# 02_BTB_IO.net
KiCad netlist of a schematic drawn in Altium Designer
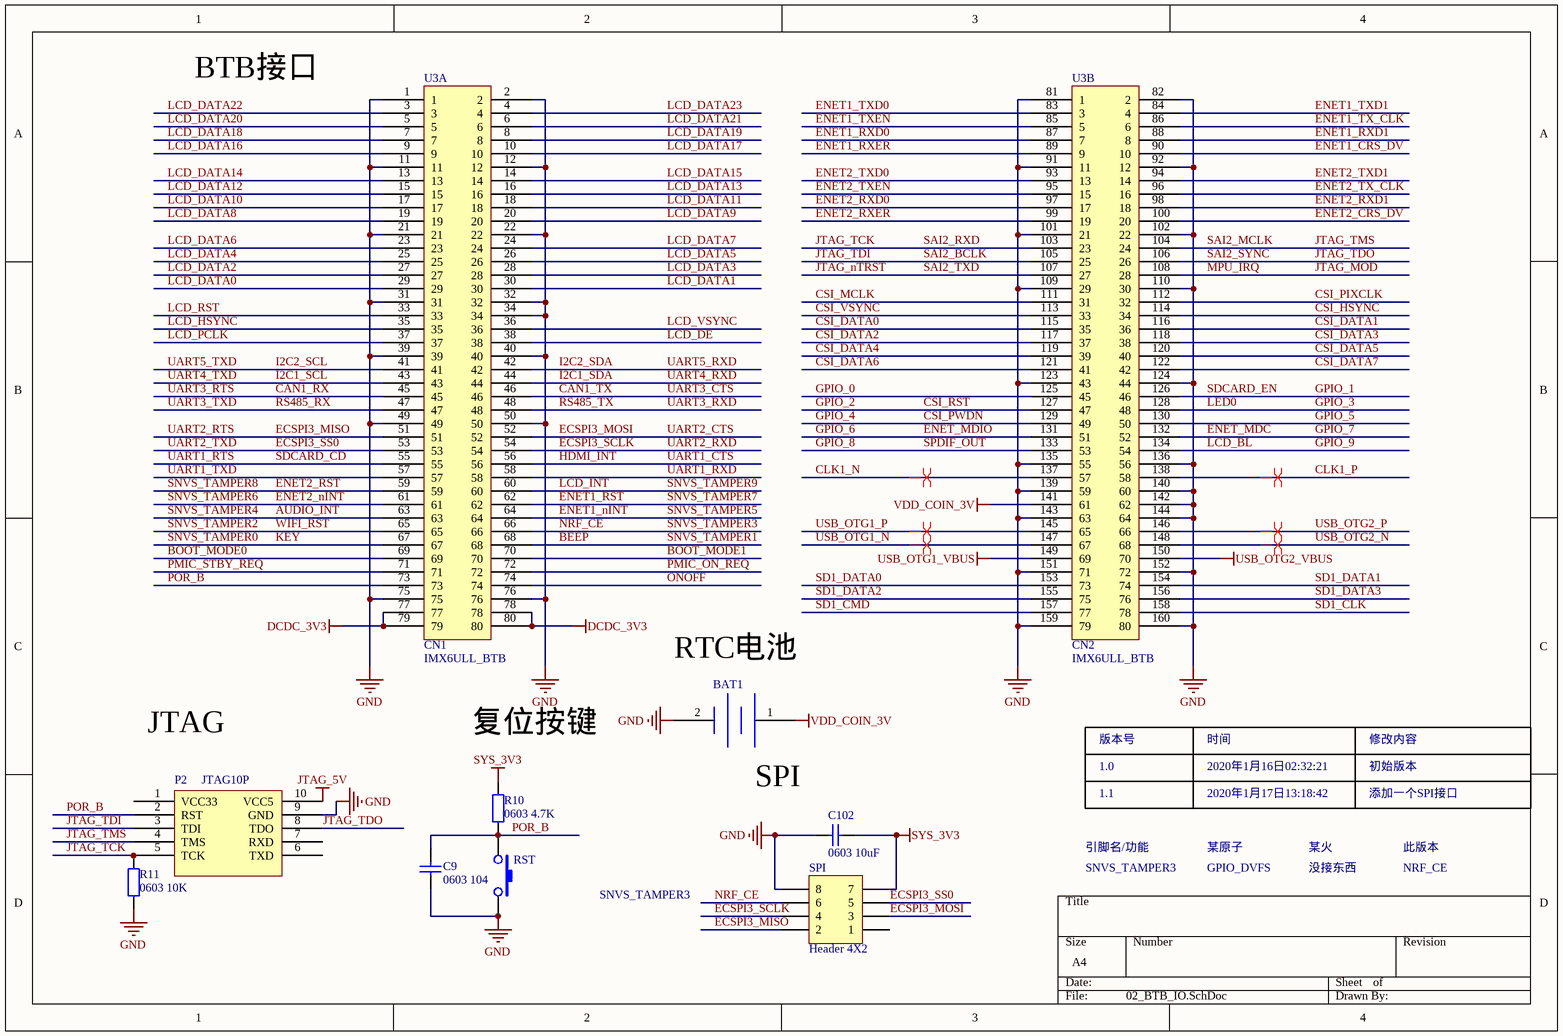
[diagram p0: 02_BTB_IO.SchDoc]

(export (version "E")
  (design (tool "Eeschema 10.0.6"))
  (components
    (comp (ref "BAT1")
      (value "~")
      (footprint "CR1220")
      (libsource (lib "Integrated_Library2") (part "RTC电池"))
    )
    (comp (ref "C9")
      (value "0603 104")
      (footprint "LC-0603_C")
      (description "贴片电容")
      (libsource (lib "JLC") (part "0603 1.5nF (152) 10% 50V"))
    )
    (comp (ref "C102")
      (value "0603 10uF")
      (footprint "LC-0603_C")
      (description "贴片电容")
      (libsource (lib "JLC") (part "0603 1.5nF (152) 10% 50V"))
    )
    (comp (ref "P2")
      (value "JTAG10P")
      (footprint "JTAG10P2")
      (libsource (lib "Integrated_Library2") (part "JTAG10P"))
    )
    (comp (ref "R10")
      (value "0603 4.7K")
      (footprint "LC-0603_R")
      (description "贴片电阻")
      (libsource (lib "JLC") (part "0603 1.1KΩ (1101) 1%"))
    )
    (comp (ref "R11")
      (value "0603 10K")
      (footprint "LC-0603_R")
      (description "贴片电阻")
      (libsource (lib "JLC") (part "0603 1.1KΩ (1101) 1%"))
    )
    (comp (ref "RST") (value "~") (footprint "KEY2") (libsource (lib "Integrated_Library2") (part "KEY")))
    (comp (ref "SPI")
      (value "Header 4X2")
      (footprint "HDR2X4")
      (description "Header, 4-Pin, Dual row")
      (fields (field (name "PUBLISHER") "Altium Limited"))
      (libsource (lib "Miscellaneous Connectors") (part "Header 4X2"))
    )
    (comp (ref "U3")
      (value "IMX6ULL_BTB")
      (footprint "IMX6ULL_BTB")
      (libsource (lib "Integrated_Library2") (part "IMX6ULL_BTB"))
    )
  )
  (nets
    (net (code "1") (name "/AUDIO_INT") (class "Default")
      (node (ref "U3") (pin "63") (pinfunction "63_63") (pintype "passive"))
    )
    (net (code "2") (name "/BEEP") (class "Default")
      (node (ref "U3") (pin "68") (pinfunction "68_68") (pintype "passive"))
    )
    (net (code "3") (name "/BOOT_MODE0") (class "Default")
      (node (ref "U3") (pin "69") (pinfunction "69_69") (pintype "passive"))
    )
    (net (code "4") (name "/BOOT_MODE1") (class "Default")
      (node (ref "U3") (pin "70") (pinfunction "70_70") (pintype "passive"))
    )
    (net (code "5") (name "/CAN1_RX") (class "Default")
      (node (ref "U3") (pin "45") (pinfunction "45_45") (pintype "passive"))
    )
    (net (code "6") (name "/CAN1_TX") (class "Default")
      (node (ref "U3") (pin "46") (pinfunction "46_46") (pintype "passive"))
    )
    (net (code "7") (name "/CLK1_N") (class "Default")
      (node (ref "U3") (pin "137") (pinfunction "57_137") (pintype "passive"))
    )
    (net (code "8") (name "/CLK1_P") (class "Default")
      (node (ref "U3") (pin "138") (pinfunction "58_138") (pintype "passive"))
    )
    (net (code "9") (name "/CSI_DATA0") (class "Default")
      (node (ref "U3") (pin "115") (pinfunction "35_115") (pintype "passive"))
    )
    (net (code "10") (name "/CSI_DATA1") (class "Default")
      (node (ref "U3") (pin "116") (pinfunction "36_116") (pintype "passive"))
    )
    (net (code "11") (name "/CSI_DATA2") (class "Default")
      (node (ref "U3") (pin "117") (pinfunction "37_117") (pintype "passive"))
    )
    (net (code "12") (name "/CSI_DATA3") (class "Default")
      (node (ref "U3") (pin "118") (pinfunction "38_118") (pintype "passive"))
    )
    (net (code "13") (name "/CSI_DATA4") (class "Default")
      (node (ref "U3") (pin "119") (pinfunction "39_119") (pintype "passive"))
    )
    (net (code "14") (name "/CSI_DATA5") (class "Default")
      (node (ref "U3") (pin "120") (pinfunction "40_120") (pintype "passive"))
    )
    (net (code "15") (name "/CSI_DATA6") (class "Default")
      (node (ref "U3") (pin "121") (pinfunction "41_121") (pintype "passive"))
    )
    (net (code "16") (name "/CSI_DATA7") (class "Default")
      (node (ref "U3") (pin "122") (pinfunction "42_122") (pintype "passive"))
    )
    (net (code "17") (name "/CSI_HSYNC") (class "Default")
      (node (ref "U3") (pin "114") (pinfunction "34_114") (pintype "passive"))
    )
    (net (code "18") (name "/CSI_MCLK") (class "Default")
      (node (ref "U3") (pin "111") (pinfunction "31_111") (pintype "passive"))
    )
    (net (code "19") (name "/CSI_PIXCLK") (class "Default")
      (node (ref "U3") (pin "112") (pinfunction "32_112") (pintype "passive"))
    )
    (net (code "20") (name "/CSI_PWDN") (class "Default")
      (node (ref "U3") (pin "129") (pinfunction "49_129") (pintype "passive"))
    )
    (net (code "21") (name "/CSI_RST") (class "Default")
      (node (ref "U3") (pin "127") (pinfunction "47_127") (pintype "passive"))
    )
    (net (code "22") (name "/CSI_VSYNC") (class "Default")
      (node (ref "U3") (pin "113") (pinfunction "33_113") (pintype "passive"))
    )
    (net (code "23") (name "/ECSPI3_MISO") (class "Default")
      (node (ref "SPI") (pin "2") (pinfunction "2_2") (pintype "passive"))
      (node (ref "U3") (pin "51") (pinfunction "51_51") (pintype "passive"))
    )
    (net (code "24") (name "/ECSPI3_MOSI") (class "Default")
      (node (ref "SPI") (pin "3") (pinfunction "3_3") (pintype "passive"))
      (node (ref "U3") (pin "52") (pinfunction "52_52") (pintype "passive"))
    )
    (net (code "25") (name "/ECSPI3_SCLK") (class "Default")
      (node (ref "SPI") (pin "4") (pinfunction "4_4") (pintype "passive"))
      (node (ref "U3") (pin "54") (pinfunction "54_54") (pintype "passive"))
    )
    (net (code "26") (name "/ECSPI3_SS0") (class "Default")
      (node (ref "SPI") (pin "5") (pinfunction "5_5") (pintype "passive"))
      (node (ref "U3") (pin "53") (pinfunction "53_53") (pintype "passive"))
    )
    (net (code "27") (name "/ENET1_CRS_DV") (class "Default")
      (node (ref "U3") (pin "90") (pinfunction "10_90") (pintype "passive"))
    )
    (net (code "28") (name "/ENET1_RST") (class "Default")
      (node (ref "U3") (pin "62") (pinfunction "62_62") (pintype "passive"))
    )
    (net (code "29") (name "/ENET1_RXD0") (class "Default")
      (node (ref "U3") (pin "87") (pinfunction "7_87") (pintype "passive"))
    )
    (net (code "30") (name "/ENET1_RXD1") (class "Default")
      (node (ref "U3") (pin "88") (pinfunction "8_88") (pintype "passive"))
    )
    (net (code "31") (name "/ENET1_RXER") (class "Default")
      (node (ref "U3") (pin "89") (pinfunction "9_89") (pintype "passive"))
    )
    (net (code "32") (name "/ENET1_TXD0") (class "Default")
      (node (ref "U3") (pin "83") (pinfunction "3_83") (pintype "passive"))
    )
    (net (code "33") (name "/ENET1_TXD1") (class "Default")
      (node (ref "U3") (pin "84") (pinfunction "4_84") (pintype "passive"))
    )
    (net (code "34") (name "/ENET1_TXEN") (class "Default")
      (node (ref "U3") (pin "85") (pinfunction "5_85") (pintype "passive"))
    )
    (net (code "35") (name "/ENET1_TX_CLK") (class "Default")
      (node (ref "U3") (pin "86") (pinfunction "6_86") (pintype "passive"))
    )
    (net (code "36") (name "/ENET1_nINT") (class "Default")
      (node (ref "U3") (pin "64") (pinfunction "64_64") (pintype "passive"))
    )
    (net (code "37") (name "/ENET2_CRS_DV") (class "Default")
      (node (ref "U3") (pin "100") (pinfunction "20_100") (pintype "passive"))
    )
    (net (code "38") (name "/ENET2_RST") (class "Default")
      (node (ref "U3") (pin "59") (pinfunction "59_59") (pintype "passive"))
    )
    (net (code "39") (name "/ENET2_RXD0") (class "Default")
      (node (ref "U3") (pin "97") (pinfunction "17_97") (pintype "passive"))
    )
    (net (code "40") (name "/ENET2_RXD1") (class "Default")
      (node (ref "U3") (pin "98") (pinfunction "18_98") (pintype "passive"))
    )
    (net (code "41") (name "/ENET2_RXER") (class "Default")
      (node (ref "U3") (pin "99") (pinfunction "19_99") (pintype "passive"))
    )
    (net (code "42") (name "/ENET2_TXD0") (class "Default")
      (node (ref "U3") (pin "93") (pinfunction "13_93") (pintype "passive"))
    )
    (net (code "43") (name "/ENET2_TXD1") (class "Default")
      (node (ref "U3") (pin "94") (pinfunction "14_94") (pintype "passive"))
    )
    (net (code "44") (name "/ENET2_TXEN") (class "Default")
      (node (ref "U3") (pin "95") (pinfunction "15_95") (pintype "passive"))
    )
    (net (code "45") (name "/ENET2_TX_CLK") (class "Default")
      (node (ref "U3") (pin "96") (pinfunction "16_96") (pintype "passive"))
    )
    (net (code "46") (name "/ENET2_nINT") (class "Default")
      (node (ref "U3") (pin "61") (pinfunction "61_61") (pintype "passive"))
    )
    (net (code "47") (name "/ENET_MDC") (class "Default")
      (node (ref "U3") (pin "132") (pinfunction "52_132") (pintype "passive"))
    )
    (net (code "48") (name "/ENET_MDIO") (class "Default")
      (node (ref "U3") (pin "131") (pinfunction "51_131") (pintype "passive"))
    )
    (net (code "49") (name "/GPIO_0") (class "Default")
      (node (ref "U3") (pin "125") (pinfunction "45_125") (pintype "passive"))
    )
    (net (code "50") (name "/GPIO_1") (class "Default")
      (node (ref "U3") (pin "126") (pinfunction "46_126") (pintype "passive"))
    )
    (net (code "51") (name "/GPIO_3") (class "Default")
      (node (ref "U3") (pin "128") (pinfunction "48_128") (pintype "passive"))
    )
    (net (code "52") (name "/GPIO_5") (class "Default")
      (node (ref "U3") (pin "130") (pinfunction "50_130") (pintype "passive"))
    )
    (net (code "53") (name "/GPIO_8") (class "Default")
      (node (ref "U3") (pin "133") (pinfunction "53_133") (pintype "passive"))
    )
    (net (code "54") (name "/GPIO_9") (class "Default")
      (node (ref "U3") (pin "134") (pinfunction "54_134") (pintype "passive"))
    )
    (net (code "55") (name "/HDMI_INT") (class "Default")
      (node (ref "U3") (pin "56") (pinfunction "56_56") (pintype "passive"))
    )
    (net (code "56") (name "/I2C1_SCL") (class "Default")
      (node (ref "U3") (pin "43") (pinfunction "43_43") (pintype "passive"))
    )
    (net (code "57") (name "/I2C1_SDA") (class "Default")
      (node (ref "U3") (pin "44") (pinfunction "44_44") (pintype "passive"))
    )
    (net (code "58") (name "/I2C2_SCL") (class "Default")
      (node (ref "U3") (pin "41") (pinfunction "41_41") (pintype "passive"))
    )
    (net (code "59") (name "/I2C2_SDA") (class "Default")
      (node (ref "U3") (pin "42") (pinfunction "42_42") (pintype "passive"))
    )
    (net (code "60") (name "/JTAG_MOD") (class "Default")
      (node (ref "U3") (pin "108") (pinfunction "28_108") (pintype "passive"))
    )
    (net (code "61") (name "/JTAG_TCK") (class "Default")
      (node (ref "P2") (pin "5") (pinfunction "TCK_5") (pintype "passive"))
      (node (ref "R11") (pin "2") (pinfunction "2_2") (pintype "passive"))
      (node (ref "U3") (pin "103") (pinfunction "23_103") (pintype "passive"))
    )
    (net (code "62") (name "/JTAG_TDI") (class "Default")
      (node (ref "P2") (pin "3") (pinfunction "TDI_3") (pintype "passive"))
      (node (ref "U3") (pin "105") (pinfunction "25_105") (pintype "passive"))
    )
    (net (code "63") (name "/JTAG_TDO") (class "Default")
      (node (ref "P2") (pin "8") (pinfunction "TDO_8") (pintype "passive"))
      (node (ref "U3") (pin "106") (pinfunction "26_106") (pintype "passive"))
    )
    (net (code "64") (name "/JTAG_TMS") (class "Default")
      (node (ref "P2") (pin "4") (pinfunction "TMS_4") (pintype "passive"))
      (node (ref "U3") (pin "104") (pinfunction "24_104") (pintype "passive"))
    )
    (net (code "65") (name "/JTAG_nTRST") (class "Default")
      (node (ref "U3") (pin "107") (pinfunction "27_107") (pintype "passive"))
    )
    (net (code "66") (name "/KEY") (class "Default")
      (node (ref "U3") (pin "67") (pinfunction "67_67") (pintype "passive"))
    )
    (net (code "67") (name "/LCD_DATA0") (class "Default")
      (node (ref "U3") (pin "29") (pinfunction "29_29") (pintype "passive"))
    )
    (net (code "68") (name "/LCD_DATA1") (class "Default")
      (node (ref "U3") (pin "30") (pinfunction "30_30") (pintype "passive"))
    )
    (net (code "69") (name "/LCD_DATA2") (class "Default")
      (node (ref "U3") (pin "27") (pinfunction "27_27") (pintype "passive"))
    )
    (net (code "70") (name "/LCD_DATA3") (class "Default")
      (node (ref "U3") (pin "28") (pinfunction "28_28") (pintype "passive"))
    )
    (net (code "71") (name "/LCD_DATA4") (class "Default")
      (node (ref "U3") (pin "25") (pinfunction "25_25") (pintype "passive"))
    )
    (net (code "72") (name "/LCD_DATA5") (class "Default")
      (node (ref "U3") (pin "26") (pinfunction "26_26") (pintype "passive"))
    )
    (net (code "73") (name "/LCD_DATA6") (class "Default")
      (node (ref "U3") (pin "23") (pinfunction "23_23") (pintype "passive"))
    )
    (net (code "74") (name "/LCD_DATA7") (class "Default")
      (node (ref "U3") (pin "24") (pinfunction "24_24") (pintype "passive"))
    )
    (net (code "75") (name "/LCD_DATA8") (class "Default")
      (node (ref "U3") (pin "19") (pinfunction "19_19") (pintype "passive"))
    )
    (net (code "76") (name "/LCD_DATA9") (class "Default")
      (node (ref "U3") (pin "20") (pinfunction "20_20") (pintype "passive"))
    )
    (net (code "77") (name "/LCD_DATA10") (class "Default")
      (node (ref "U3") (pin "17") (pinfunction "17_17") (pintype "passive"))
    )
    (net (code "78") (name "/LCD_DATA11") (class "Default")
      (node (ref "U3") (pin "18") (pinfunction "18_18") (pintype "passive"))
    )
    (net (code "79") (name "/LCD_DATA12") (class "Default")
      (node (ref "U3") (pin "15") (pinfunction "15_15") (pintype "passive"))
    )
    (net (code "80") (name "/LCD_DATA13") (class "Default")
      (node (ref "U3") (pin "16") (pinfunction "16_16") (pintype "passive"))
    )
    (net (code "81") (name "/LCD_DATA14") (class "Default")
      (node (ref "U3") (pin "13") (pinfunction "13_13") (pintype "passive"))
    )
    (net (code "82") (name "/LCD_DATA15") (class "Default")
      (node (ref "U3") (pin "14") (pinfunction "14_14") (pintype "passive"))
    )
    (net (code "83") (name "/LCD_DATA16") (class "Default")
      (node (ref "U3") (pin "9") (pinfunction "9_9") (pintype "passive"))
    )
    (net (code "84") (name "/LCD_DATA17") (class "Default")
      (node (ref "U3") (pin "10") (pinfunction "10_10") (pintype "passive"))
    )
    (net (code "85") (name "/LCD_DATA18") (class "Default")
      (node (ref "U3") (pin "7") (pinfunction "7_7") (pintype "passive"))
    )
    (net (code "86") (name "/LCD_DATA19") (class "Default")
      (node (ref "U3") (pin "8") (pinfunction "8_8") (pintype "passive"))
    )
    (net (code "87") (name "/LCD_DATA20") (class "Default")
      (node (ref "U3") (pin "5") (pinfunction "5_5") (pintype "passive"))
    )
    (net (code "88") (name "/LCD_DATA21") (class "Default")
      (node (ref "U3") (pin "6") (pinfunction "6_6") (pintype "passive"))
    )
    (net (code "89") (name "/LCD_DATA22") (class "Default")
      (node (ref "U3") (pin "3") (pinfunction "3_3") (pintype "passive"))
    )
    (net (code "90") (name "/LCD_DATA23") (class "Default")
      (node (ref "U3") (pin "4") (pinfunction "4_4") (pintype "passive"))
    )
    (net (code "91") (name "/LCD_DE") (class "Default")
      (node (ref "U3") (pin "38") (pinfunction "38_38") (pintype "passive"))
    )
    (net (code "92") (name "/LCD_HSYNC") (class "Default")
      (node (ref "U3") (pin "35") (pinfunction "35_35") (pintype "passive"))
    )
    (net (code "93") (name "/LCD_INT") (class "Default")
      (node (ref "U3") (pin "60") (pinfunction "60_60") (pintype "passive"))
    )
    (net (code "94") (name "/LCD_PCLK") (class "Default")
      (node (ref "U3") (pin "37") (pinfunction "37_37") (pintype "passive"))
    )
    (net (code "95") (name "/LCD_RST") (class "Default")
      (node (ref "U3") (pin "33") (pinfunction "33_33") (pintype "passive"))
    )
    (net (code "96") (name "/LCD_VSYNC") (class "Default")
      (node (ref "U3") (pin "36") (pinfunction "36_36") (pintype "passive"))
    )
    (net (code "97") (name "/NRF_CE") (class "Default")
      (node (ref "SPI") (pin "6") (pinfunction "6_6") (pintype "passive"))
      (node (ref "U3") (pin "66") (pinfunction "66_66") (pintype "passive"))
    )
    (net (code "98") (name "/ONOFF") (class "Default")
      (node (ref "U3") (pin "74") (pinfunction "74_74") (pintype "passive"))
    )
    (net (code "99") (name "/PMIC_ON_REQ") (class "Default")
      (node (ref "U3") (pin "72") (pinfunction "72_72") (pintype "passive"))
    )
    (net (code "100") (name "/PMIC_STBY_REQ") (class "Default")
      (node (ref "U3") (pin "71") (pinfunction "71_71") (pintype "passive"))
    )
    (net (code "101") (name "/POR_B") (class "Default")
      (node (ref "C9") (pin "2") (pinfunction "2_2") (pintype "passive"))
      (node (ref "P2") (pin "2") (pinfunction "RST_2") (pintype "passive"))
      (node (ref "R10") (pin "1") (pinfunction "1_1") (pintype "passive"))
      (node (ref "RST") (pin "1") (pinfunction "1_1") (pintype "passive"))
      (node (ref "U3") (pin "73") (pinfunction "73_73") (pintype "passive"))
    )
    (net (code "102") (name "/RS485_RX") (class "Default")
      (node (ref "U3") (pin "47") (pinfunction "47_47") (pintype "passive"))
    )
    (net (code "103") (name "/RS485_TX") (class "Default")
      (node (ref "U3") (pin "48") (pinfunction "48_48") (pintype "passive"))
    )
    (net (code "104") (name "/SD1_CLK") (class "Default")
      (node (ref "U3") (pin "158") (pinfunction "78_158") (pintype "passive"))
    )
    (net (code "105") (name "/SD1_CMD") (class "Default")
      (node (ref "U3") (pin "157") (pinfunction "77_157") (pintype "passive"))
    )
    (net (code "106") (name "/SD1_DATA0") (class "Default")
      (node (ref "U3") (pin "153") (pinfunction "73_153") (pintype "passive"))
    )
    (net (code "107") (name "/SD1_DATA1") (class "Default")
      (node (ref "U3") (pin "154") (pinfunction "74_154") (pintype "passive"))
    )
    (net (code "108") (name "/SD1_DATA2") (class "Default")
      (node (ref "U3") (pin "155") (pinfunction "75_155") (pintype "passive"))
    )
    (net (code "109") (name "/SD1_DATA3") (class "Default")
      (node (ref "U3") (pin "156") (pinfunction "76_156") (pintype "passive"))
    )
    (net (code "110") (name "/SDCARD_CD") (class "Default")
      (node (ref "U3") (pin "55") (pinfunction "55_55") (pintype "passive"))
    )
    (net (code "111") (name "/SNVS_TAMPER2") (class "Default")
      (node (ref "U3") (pin "65") (pinfunction "65_65") (pintype "passive"))
    )
    (net (code "112") (name "/UART1_RXD") (class "Default")
      (node (ref "U3") (pin "58") (pinfunction "58_58") (pintype "passive"))
    )
    (net (code "113") (name "/UART1_TXD") (class "Default")
      (node (ref "U3") (pin "57") (pinfunction "57_57") (pintype "passive"))
    )
    (net (code "114") (name "/USB_OTG1_N") (class "Default")
      (node (ref "U3") (pin "147") (pinfunction "67_147") (pintype "passive"))
    )
    (net (code "115") (name "/USB_OTG1_P") (class "Default")
      (node (ref "U3") (pin "145") (pinfunction "65_145") (pintype "passive"))
    )
    (net (code "116") (name "/USB_OTG2_N") (class "Default")
      (node (ref "U3") (pin "148") (pinfunction "68_148") (pintype "passive"))
    )
    (net (code "117") (name "/USB_OTG2_P") (class "Default")
      (node (ref "U3") (pin "146") (pinfunction "66_146") (pintype "passive"))
    )
    (net (code "118") (name "DCDC_3V3") (class "Default")
      (node (ref "U3") (pin "77") (pinfunction "77_77") (pintype "passive"))
      (node (ref "U3") (pin "78") (pinfunction "78_78") (pintype "passive"))
      (node (ref "U3") (pin "79") (pinfunction "79_79") (pintype "passive"))
      (node (ref "U3") (pin "80") (pinfunction "80_80") (pintype "passive"))
    )
    (net (code "119") (name "GND") (class "Default")
      (node (ref "BAT1") (pin "2") (pinfunction "2_2") (pintype "passive"))
      (node (ref "C102") (pin "1") (pinfunction "1_1") (pintype "passive"))
      (node (ref "C9") (pin "1") (pinfunction "1_1") (pintype "passive"))
      (node (ref "P2") (pin "9") (pinfunction "GND_9") (pintype "passive"))
      (node (ref "R11") (pin "1") (pinfunction "1_1") (pintype "passive"))
      (node (ref "RST") (pin "2") (pinfunction "2_2") (pintype "passive"))
      (node (ref "SPI") (pin "8") (pinfunction "8_8") (pintype "passive"))
      (node (ref "U3") (pin "1") (pinfunction "1_1") (pintype "passive"))
      (node (ref "U3") (pin "101") (pinfunction "21_101") (pintype "passive"))
      (node (ref "U3") (pin "102") (pinfunction "22_102") (pintype "passive"))
      (node (ref "U3") (pin "109") (pinfunction "29_109") (pintype "passive"))
      (node (ref "U3") (pin "11") (pinfunction "11_11") (pintype "passive"))
      (node (ref "U3") (pin "110") (pinfunction "30_110") (pintype "passive"))
      (node (ref "U3") (pin "12") (pinfunction "12_12") (pintype "passive"))
      (node (ref "U3") (pin "123") (pinfunction "43_123") (pintype "passive"))
      (node (ref "U3") (pin "124") (pinfunction "44_124") (pintype "passive"))
      (node (ref "U3") (pin "135") (pinfunction "55_135") (pintype "passive"))
      (node (ref "U3") (pin "136") (pinfunction "56_136") (pintype "passive"))
      (node (ref "U3") (pin "139") (pinfunction "59_139") (pintype "passive"))
      (node (ref "U3") (pin "140") (pinfunction "60_140") (pintype "passive"))
      (node (ref "U3") (pin "142") (pinfunction "62_142") (pintype "passive"))
      (node (ref "U3") (pin "143") (pinfunction "63_143") (pintype "passive"))
      (node (ref "U3") (pin "144") (pinfunction "64_144") (pintype "passive"))
      (node (ref "U3") (pin "151") (pinfunction "71_151") (pintype "passive"))
      (node (ref "U3") (pin "152") (pinfunction "72_152") (pintype "passive"))
      (node (ref "U3") (pin "159") (pinfunction "79_159") (pintype "passive"))
      (node (ref "U3") (pin "160") (pinfunction "80_160") (pintype "passive"))
      (node (ref "U3") (pin "2") (pinfunction "2_2") (pintype "passive"))
      (node (ref "U3") (pin "21") (pinfunction "21_21") (pintype "passive"))
      (node (ref "U3") (pin "22") (pinfunction "22_22") (pintype "passive"))
      (node (ref "U3") (pin "31") (pinfunction "31_31") (pintype "passive"))
      (node (ref "U3") (pin "32") (pinfunction "32_32") (pintype "passive"))
      (node (ref "U3") (pin "34") (pinfunction "34_34") (pintype "passive"))
      (node (ref "U3") (pin "39") (pinfunction "39_39") (pintype "passive"))
      (node (ref "U3") (pin "40") (pinfunction "40_40") (pintype "passive"))
      (node (ref "U3") (pin "49") (pinfunction "49_49") (pintype "passive"))
      (node (ref "U3") (pin "50") (pinfunction "50_50") (pintype "passive"))
      (node (ref "U3") (pin "75") (pinfunction "75_75") (pintype "passive"))
      (node (ref "U3") (pin "76") (pinfunction "76_76") (pintype "passive"))
      (node (ref "U3") (pin "81") (pinfunction "1_81") (pintype "passive"))
      (node (ref "U3") (pin "82") (pinfunction "2_82") (pintype "passive"))
      (node (ref "U3") (pin "91") (pinfunction "11_91") (pintype "passive"))
      (node (ref "U3") (pin "92") (pinfunction "12_92") (pintype "passive"))
    )
    (net (code "120") (name "JTAG_5V") (class "Default")
      (node (ref "P2") (pin "10") (pinfunction "VCC5_10") (pintype "passive"))
    )
    (net (code "121") (name "SYS_3V3") (class "Default")
      (node (ref "C102") (pin "2") (pinfunction "2_2") (pintype "passive"))
      (node (ref "R10") (pin "2") (pinfunction "2_2") (pintype "passive"))
      (node (ref "SPI") (pin "7") (pinfunction "7_7") (pintype "passive"))
    )
    (net (code "122") (name "USB_OTG1_VBUS") (class "Default")
      (node (ref "U3") (pin "149") (pinfunction "69_149") (pintype "passive"))
    )
    (net (code "123") (name "USB_OTG2_VBUS") (class "Default")
      (node (ref "U3") (pin "150") (pinfunction "70_150") (pintype "passive"))
    )
    (net (code "124") (name "VDD_COIN_3V") (class "Default")
      (node (ref "BAT1") (pin "1") (pinfunction "1_1") (pintype "passive"))
      (node (ref "U3") (pin "141") (pinfunction "61_141") (pintype "passive"))
    )
    (net (code "125") (name "unconnected-(P2-RXD-Pad7)") (class "Default")
      (node (ref "P2") (pin "7") (pinfunction "RXD_7") (pintype "passive"))
    )
    (net (code "126") (name "unconnected-(P2-TXD-Pad6)") (class "Default")
      (node (ref "P2") (pin "6") (pinfunction "TXD_6") (pintype "passive"))
    )
    (net (code "127") (name "unconnected-(P2-VCC33-Pad1)") (class "Default")
      (node (ref "P2") (pin "1") (pinfunction "VCC33_1") (pintype "passive"))
    )
    (net (code "128") (name "unconnected-(SPI-Pad1)") (class "Default")
      (node (ref "SPI") (pin "1") (pinfunction "1_1") (pintype "passive"))
    )
  )
)
